# i2c_programmer.net
KiCad netlist of a schematic drawn in EAGLE
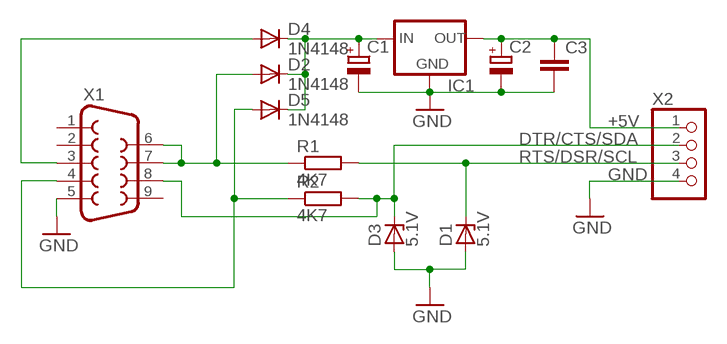
[diagram p0: schematic, sheet 1]

(export (version "E")
  (design (tool "Eeschema 10.0.6"))
  (components
    (comp (ref "C1")
      (value "CPOL-EUE2.5-6")
      (footprint "eagle-import:E2,5-6")
      (libsource (lib "eagle-import") (part "CPOL-EUE2.5-6"))
    )
    (comp (ref "C2")
      (value "CPOL-EUE2.5-6")
      (footprint "eagle-import:E2,5-6")
      (libsource (lib "eagle-import") (part "CPOL-EUE2.5-6"))
    )
    (comp (ref "C3")
      (value "C-EU025-025X050")
      (footprint "eagle-import:C025-025X050")
      (libsource (lib "eagle-import") (part "C-EU025-025X050"))
    )
    (comp (ref "D1")
      (value "5.1V")
      (footprint "eagle-import:DO41Z10")
      (libsource (lib "eagle-import") (part "1N4728"))
    )
    (comp (ref "D2")
      (value "1N4148")
      (footprint "eagle-import:DO41-10")
      (libsource (lib "eagle-import") (part "1N4004A"))
    )
    (comp (ref "D3")
      (value "5.1V")
      (footprint "eagle-import:DO41Z10")
      (libsource (lib "eagle-import") (part "1N4728"))
    )
    (comp (ref "D4")
      (value "1N4148")
      (footprint "eagle-import:DO41-10")
      (libsource (lib "eagle-import") (part "1N4004A"))
    )
    (comp (ref "D5")
      (value "1N4148")
      (footprint "eagle-import:DO41-10")
      (libsource (lib "eagle-import") (part "1N4004A"))
    )
    (comp (ref "IC1")
      (value "78LXX")
      (footprint "eagle-import:78LXX")
      (libsource (lib "eagle-import") (part "78LXX"))
    )
    (comp (ref "R1")
      (value "4K7")
      (footprint "eagle-import:0207_7")
      (libsource (lib "eagle-import") (part "R-EU_0207/7"))
    )
    (comp (ref "R2")
      (value "4K7")
      (footprint "eagle-import:0207_7")
      (libsource (lib "eagle-import") (part "R-EU_0207/7"))
    )
    (comp (ref "X1")
      (value "F09HP")
      (footprint "eagle-import:F09HP")
      (libsource (lib "eagle-import") (part "F09HP"))
    )
    (comp (ref "X2")
      (value "22-23-2041")
      (footprint "eagle-import:22-23-2041")
      (libsource (lib "eagle-import") (part "22-23-2041"))
    )
  )
  (nets
    (net (code "1") (name "/+5V") (class "Default")
      (node (ref "C2") (pin "+") (pinfunction "+_+") (pintype "passive"))
      (node (ref "C3") (pin "1") (pinfunction "1_1") (pintype "passive"))
      (node (ref "IC1") (pin "OUT") (pinfunction "OUT_OUT") (pintype "passive"))
      (node (ref "X2") (pin "1") (pinfunction "1_1") (pintype "passive"))
    )
    (net (code "2") (name "/DTR{slash}CTS{slash}SDA") (class "Default")
      (node (ref "D3") (pin "C") (pinfunction "C_C") (pintype "passive"))
      (node (ref "R2") (pin "2") (pinfunction "2_2") (pintype "passive"))
      (node (ref "X1") (pin "8") (pinfunction "8_8") (pintype "passive"))
      (node (ref "X2") (pin "2") (pinfunction "2_2") (pintype "passive"))
    )
    (net (code "3") (name "/RTS{slash}DSR{slash}SCL") (class "Default")
      (node (ref "D1") (pin "C") (pinfunction "C_C") (pintype "passive"))
      (node (ref "R1") (pin "2") (pinfunction "2_2") (pintype "passive"))
      (node (ref "X2") (pin "3") (pinfunction "3_3") (pintype "passive"))
    )
    (net (code "4") (name "GND") (class "Default")
      (node (ref "C1") (pin "-") (pinfunction "-_-") (pintype "passive"))
      (node (ref "C2") (pin "-") (pinfunction "-_-") (pintype "passive"))
      (node (ref "C3") (pin "2") (pinfunction "2_2") (pintype "passive"))
      (node (ref "D1") (pin "A") (pinfunction "A_A") (pintype "passive"))
      (node (ref "D3") (pin "A") (pinfunction "A_A") (pintype "passive"))
      (node (ref "IC1") (pin "GND") (pinfunction "GND_GND") (pintype "input"))
      (node (ref "X1") (pin "5") (pinfunction "5_5") (pintype "passive"))
      (node (ref "X2") (pin "4") (pinfunction "4_4") (pintype "passive"))
    )
    (net (code "5") (name "Net-(C1-Pad+)") (class "Default")
      (node (ref "C1") (pin "+") (pinfunction "+_+") (pintype "passive"))
      (node (ref "D2") (pin "C") (pinfunction "C_C") (pintype "passive"))
      (node (ref "D4") (pin "C") (pinfunction "C_C") (pintype "passive"))
      (node (ref "D5") (pin "C") (pinfunction "C_C") (pintype "passive"))
      (node (ref "IC1") (pin "IN") (pinfunction "IN_IN") (pintype "input"))
    )
    (net (code "6") (name "Net-(D2-PadA)") (class "Default")
      (node (ref "D2") (pin "A") (pinfunction "A_A") (pintype "passive"))
      (node (ref "R1") (pin "1") (pinfunction "1_1") (pintype "passive"))
      (node (ref "X1") (pin "6") (pinfunction "6_6") (pintype "passive"))
      (node (ref "X1") (pin "7") (pinfunction "7_7") (pintype "passive"))
    )
    (net (code "7") (name "Net-(D4-PadA)") (class "Default")
      (node (ref "D4") (pin "A") (pinfunction "A_A") (pintype "passive"))
      (node (ref "X1") (pin "3") (pinfunction "3_3") (pintype "passive"))
    )
    (net (code "8") (name "Net-(D5-PadA)") (class "Default")
      (node (ref "D5") (pin "A") (pinfunction "A_A") (pintype "passive"))
      (node (ref "R2") (pin "1") (pinfunction "1_1") (pintype "passive"))
      (node (ref "X1") (pin "4") (pinfunction "4_4") (pintype "passive"))
    )
    (net (code "9") (name "unconnected-(X1-Pad1)") (class "Default")
      (node (ref "X1") (pin "1") (pinfunction "1_1") (pintype "passive"))
    )
    (net (code "10") (name "unconnected-(X1-Pad2)") (class "Default")
      (node (ref "X1") (pin "2") (pinfunction "2_2") (pintype "passive"))
    )
    (net (code "11") (name "unconnected-(X1-Pad9)") (class "Default")
      (node (ref "X1") (pin "9") (pinfunction "9_9") (pintype "passive"))
    )
  )
)
